# LEDSlave_3.net
KiCad netlist of a schematic drawn in EAGLE
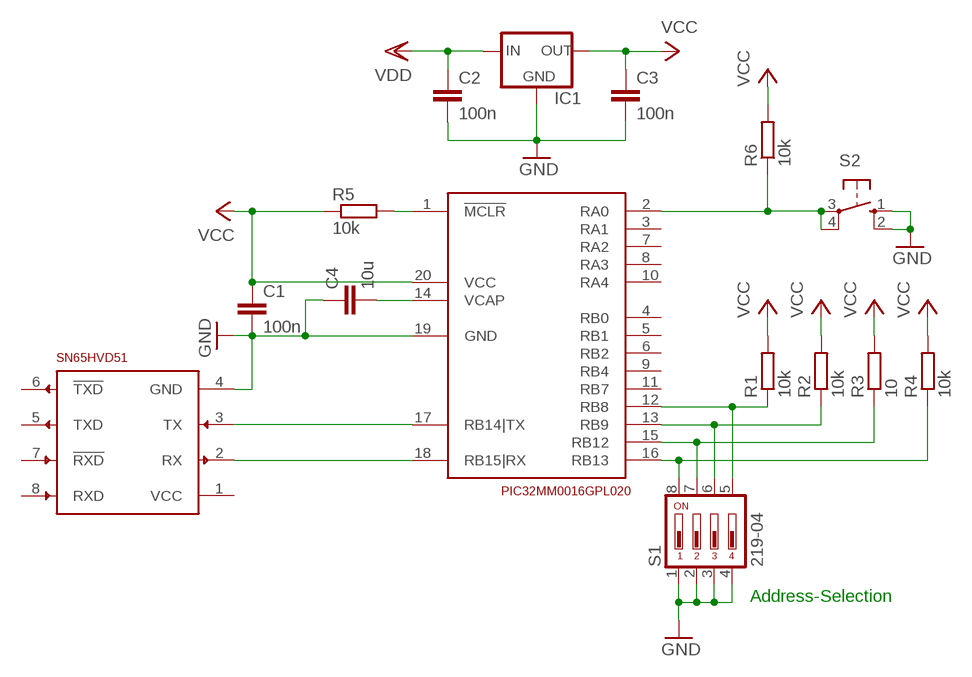
[diagram p0: schematic, sheet 1]

(export (version "E")
  (design (tool "Eeschema 10.0.6"))
  (components
    (comp (ref "C1")
      (value "100n")
      (footprint "eagle-import:C0805")
      (libsource (lib "eagle-import") (part "C-EUC0805"))
    )
    (comp (ref "C2")
      (value "100n")
      (footprint "eagle-import:C0805")
      (libsource (lib "eagle-import") (part "C-EUC0805"))
    )
    (comp (ref "C3")
      (value "100n")
      (footprint "eagle-import:C0805")
      (libsource (lib "eagle-import") (part "C-EUC0805"))
    )
    (comp (ref "C4")
      (value "10u")
      (footprint "eagle-import:C1206")
      (libsource (lib "eagle-import") (part "C-EUC1206"))
    )
    (comp (ref "IC1")
      (value "LP2950CDT-3.3")
      (footprint "eagle-import:DPACK")
      (libsource (lib "eagle-import") (part "LP2950?CDT-3.3"))
    )
    (comp (ref "R1")
      (value "10k")
      (footprint "eagle-import:R0805")
      (libsource (lib "eagle-import") (part "R-EU_R0805"))
    )
    (comp (ref "R2")
      (value "10k")
      (footprint "eagle-import:R0805")
      (libsource (lib "eagle-import") (part "R-EU_R0805"))
    )
    (comp (ref "R3")
      (value "10")
      (footprint "eagle-import:R0805")
      (libsource (lib "eagle-import") (part "R-EU_R0805"))
    )
    (comp (ref "R4")
      (value "10k")
      (footprint "eagle-import:R0805")
      (libsource (lib "eagle-import") (part "R-EU_R0805"))
    )
    (comp (ref "R5")
      (value "10k")
      (footprint "eagle-import:R0805")
      (libsource (lib "eagle-import") (part "R-EU_R0805"))
    )
    (comp (ref "R6")
      (value "10k")
      (footprint "eagle-import:R0805")
      (libsource (lib "eagle-import") (part "R-EU_R0805"))
    )
    (comp (ref "S1")
      (value "219-04")
      (footprint "eagle-import:CTS-219-04")
      (libsource (lib "eagle-import") (part "219-04"))
    )
    (comp (ref "S2")
      (value "10-XX")
      (footprint "eagle-import:B3F-10XX")
      (fields (field (name "MPN") "B3F-1000"))
      (libsource (lib "eagle-import") (part "10-XX"))
    )
    (comp (ref "U$1")
      (value "PIC32MM0016GPL020")
      (footprint "eagle-import:SSOP20")
      (libsource (lib "eagle-import") (part "PIC32MM0016GPL020"))
    )
    (comp (ref "U$2")
      (value "SN65HVD51")
      (footprint "eagle-import:SO-08")
      (libsource (lib "eagle-import") (part "SN65HVD51"))
    )
  )
  (nets
    (net (code "1") (name "GND") (class "Default")
      (node (ref "C1") (pin "2") (pinfunction "2_2") (pintype "passive"))
      (node (ref "C2") (pin "2") (pinfunction "2_2") (pintype "passive"))
      (node (ref "C3") (pin "2") (pinfunction "2_2") (pintype "passive"))
      (node (ref "C4") (pin "1") (pinfunction "1_1") (pintype "passive"))
      (node (ref "IC1") (pin "4") (pinfunction "GND_4") (pintype "input"))
      (node (ref "S1") (pin "1") (pinfunction "1_1") (pintype "passive"))
      (node (ref "S1") (pin "2") (pinfunction "2_2") (pintype "passive"))
      (node (ref "S1") (pin "3") (pinfunction "3_3") (pintype "passive"))
      (node (ref "S1") (pin "4") (pinfunction "4_4") (pintype "passive"))
      (node (ref "S2") (pin "1") (pinfunction "S_1") (pintype "passive"))
      (node (ref "S2") (pin "2") (pinfunction "S1_2") (pintype "passive"))
      (node (ref "U$1") (pin "19") (pinfunction "GND_19") (pintype "bidirectional"))
      (node (ref "U$2") (pin "4") (pinfunction "GND_4") (pintype "bidirectional"))
    )
    (net (code "2") (name "Net-(S2-P)") (class "Default")
      (node (ref "R6") (pin "1") (pinfunction "1_1") (pintype "passive"))
      (node (ref "S2") (pin "3") (pinfunction "P_3") (pintype "passive"))
      (node (ref "S2") (pin "4") (pinfunction "P1_4") (pintype "passive"))
      (node (ref "U$1") (pin "2") (pinfunction "RA0_2") (pintype "bidirectional"))
    )
    (net (code "3") (name "Net-(U$1-RB8)") (class "Default")
      (node (ref "R1") (pin "1") (pinfunction "1_1") (pintype "passive"))
      (node (ref "S1") (pin "5") (pinfunction "5_5") (pintype "passive"))
      (node (ref "U$1") (pin "12") (pinfunction "RB8_12") (pintype "bidirectional"))
    )
    (net (code "4") (name "Net-(U$1-RB9)") (class "Default")
      (node (ref "R2") (pin "1") (pinfunction "1_1") (pintype "passive"))
      (node (ref "S1") (pin "6") (pinfunction "6_6") (pintype "passive"))
      (node (ref "U$1") (pin "13") (pinfunction "RB9_13") (pintype "bidirectional"))
    )
    (net (code "5") (name "Net-(U$1-RB12)") (class "Default")
      (node (ref "R3") (pin "1") (pinfunction "1_1") (pintype "passive"))
      (node (ref "S1") (pin "7") (pinfunction "7_7") (pintype "passive"))
      (node (ref "U$1") (pin "15") (pinfunction "RB12_15") (pintype "bidirectional"))
    )
    (net (code "6") (name "Net-(U$1-RB13)") (class "Default")
      (node (ref "R4") (pin "1") (pinfunction "1_1") (pintype "passive"))
      (node (ref "S1") (pin "8") (pinfunction "8_8") (pintype "passive"))
      (node (ref "U$1") (pin "16") (pinfunction "RB13_16") (pintype "bidirectional"))
    )
    (net (code "7") (name "Net-(U$1-RB14|TX)") (class "Default")
      (node (ref "U$1") (pin "17") (pinfunction "RB14|TX_17") (pintype "bidirectional"))
      (node (ref "U$2") (pin "3") (pinfunction "TX_3") (pintype "bidirectional"))
    )
    (net (code "8") (name "Net-(U$1-RB15|RX)") (class "Default")
      (node (ref "U$1") (pin "18") (pinfunction "RB15|RX_18") (pintype "bidirectional"))
      (node (ref "U$2") (pin "2") (pinfunction "RX_2") (pintype "bidirectional"))
    )
    (net (code "9") (name "Net-(U$1-VCAP)") (class "Default")
      (node (ref "C4") (pin "2") (pinfunction "2_2") (pintype "passive"))
      (node (ref "U$1") (pin "14") (pinfunction "VCAP_14") (pintype "bidirectional"))
    )
    (net (code "10") (name "Net-(U$1-~{MCLR})") (class "Default")
      (node (ref "R5") (pin "2") (pinfunction "2_2") (pintype "passive"))
      (node (ref "U$1") (pin "1") (pinfunction "~{MCLR}_1") (pintype "bidirectional"))
    )
    (net (code "11") (name "VCC") (class "Default")
      (node (ref "C1") (pin "1") (pinfunction "1_1") (pintype "passive"))
      (node (ref "C3") (pin "1") (pinfunction "1_1") (pintype "passive"))
      (node (ref "IC1") (pin "3") (pinfunction "OUT_3") (pintype "passive"))
      (node (ref "R1") (pin "2") (pinfunction "2_2") (pintype "passive"))
      (node (ref "R2") (pin "2") (pinfunction "2_2") (pintype "passive"))
      (node (ref "R3") (pin "2") (pinfunction "2_2") (pintype "passive"))
      (node (ref "R4") (pin "2") (pinfunction "2_2") (pintype "passive"))
      (node (ref "R5") (pin "1") (pinfunction "1_1") (pintype "passive"))
      (node (ref "R6") (pin "2") (pinfunction "2_2") (pintype "passive"))
      (node (ref "U$1") (pin "20") (pinfunction "VCC_20") (pintype "bidirectional"))
    )
    (net (code "12") (name "VDD") (class "Default")
      (node (ref "C2") (pin "1") (pinfunction "1_1") (pintype "passive"))
      (node (ref "IC1") (pin "1") (pinfunction "IN_1") (pintype "input"))
    )
    (net (code "13") (name "unconnected-(U$1-RA1-Pad3)") (class "Default")
      (node (ref "U$1") (pin "3") (pinfunction "RA1_3") (pintype "bidirectional"))
    )
    (net (code "14") (name "unconnected-(U$1-RA2-Pad7)") (class "Default")
      (node (ref "U$1") (pin "7") (pinfunction "RA2_7") (pintype "bidirectional"))
    )
    (net (code "15") (name "unconnected-(U$1-RA3-Pad8)") (class "Default")
      (node (ref "U$1") (pin "8") (pinfunction "RA3_8") (pintype "bidirectional"))
    )
    (net (code "16") (name "unconnected-(U$1-RA4-Pad10)") (class "Default")
      (node (ref "U$1") (pin "10") (pinfunction "RA4_10") (pintype "bidirectional"))
    )
    (net (code "17") (name "unconnected-(U$1-RB0-Pad4)") (class "Default")
      (node (ref "U$1") (pin "4") (pinfunction "RB0_4") (pintype "bidirectional"))
    )
    (net (code "18") (name "unconnected-(U$1-RB1-Pad5)") (class "Default")
      (node (ref "U$1") (pin "5") (pinfunction "RB1_5") (pintype "bidirectional"))
    )
    (net (code "19") (name "unconnected-(U$1-RB2-Pad6)") (class "Default")
      (node (ref "U$1") (pin "6") (pinfunction "RB2_6") (pintype "bidirectional"))
    )
    (net (code "20") (name "unconnected-(U$1-RB4-Pad9)") (class "Default")
      (node (ref "U$1") (pin "9") (pinfunction "RB4_9") (pintype "bidirectional"))
    )
    (net (code "21") (name "unconnected-(U$1-RB7-Pad11)") (class "Default")
      (node (ref "U$1") (pin "11") (pinfunction "RB7_11") (pintype "bidirectional"))
    )
    (net (code "22") (name "unconnected-(U$2-RXD-Pad8)") (class "Default")
      (node (ref "U$2") (pin "8") (pinfunction "RXD_8") (pintype "bidirectional"))
    )
    (net (code "23") (name "unconnected-(U$2-TXD-Pad5)") (class "Default")
      (node (ref "U$2") (pin "5") (pinfunction "TXD_5") (pintype "bidirectional"))
    )
    (net (code "24") (name "unconnected-(U$2-VCC-Pad1)") (class "Default")
      (node (ref "U$2") (pin "1") (pinfunction "VCC_1") (pintype "bidirectional"))
    )
    (net (code "25") (name "unconnected-(U$2-~{RXD}-Pad7)") (class "Default")
      (node (ref "U$2") (pin "7") (pinfunction "~{RXD}_7") (pintype "bidirectional"))
    )
    (net (code "26") (name "unconnected-(U$2-~{TXD}-Pad6)") (class "Default")
      (node (ref "U$2") (pin "6") (pinfunction "~{TXD}_6") (pintype "bidirectional"))
    )
  )
)
